# ANALOG_TRIAC.net
KiCad netlist of a schematic drawn in Altium Designer
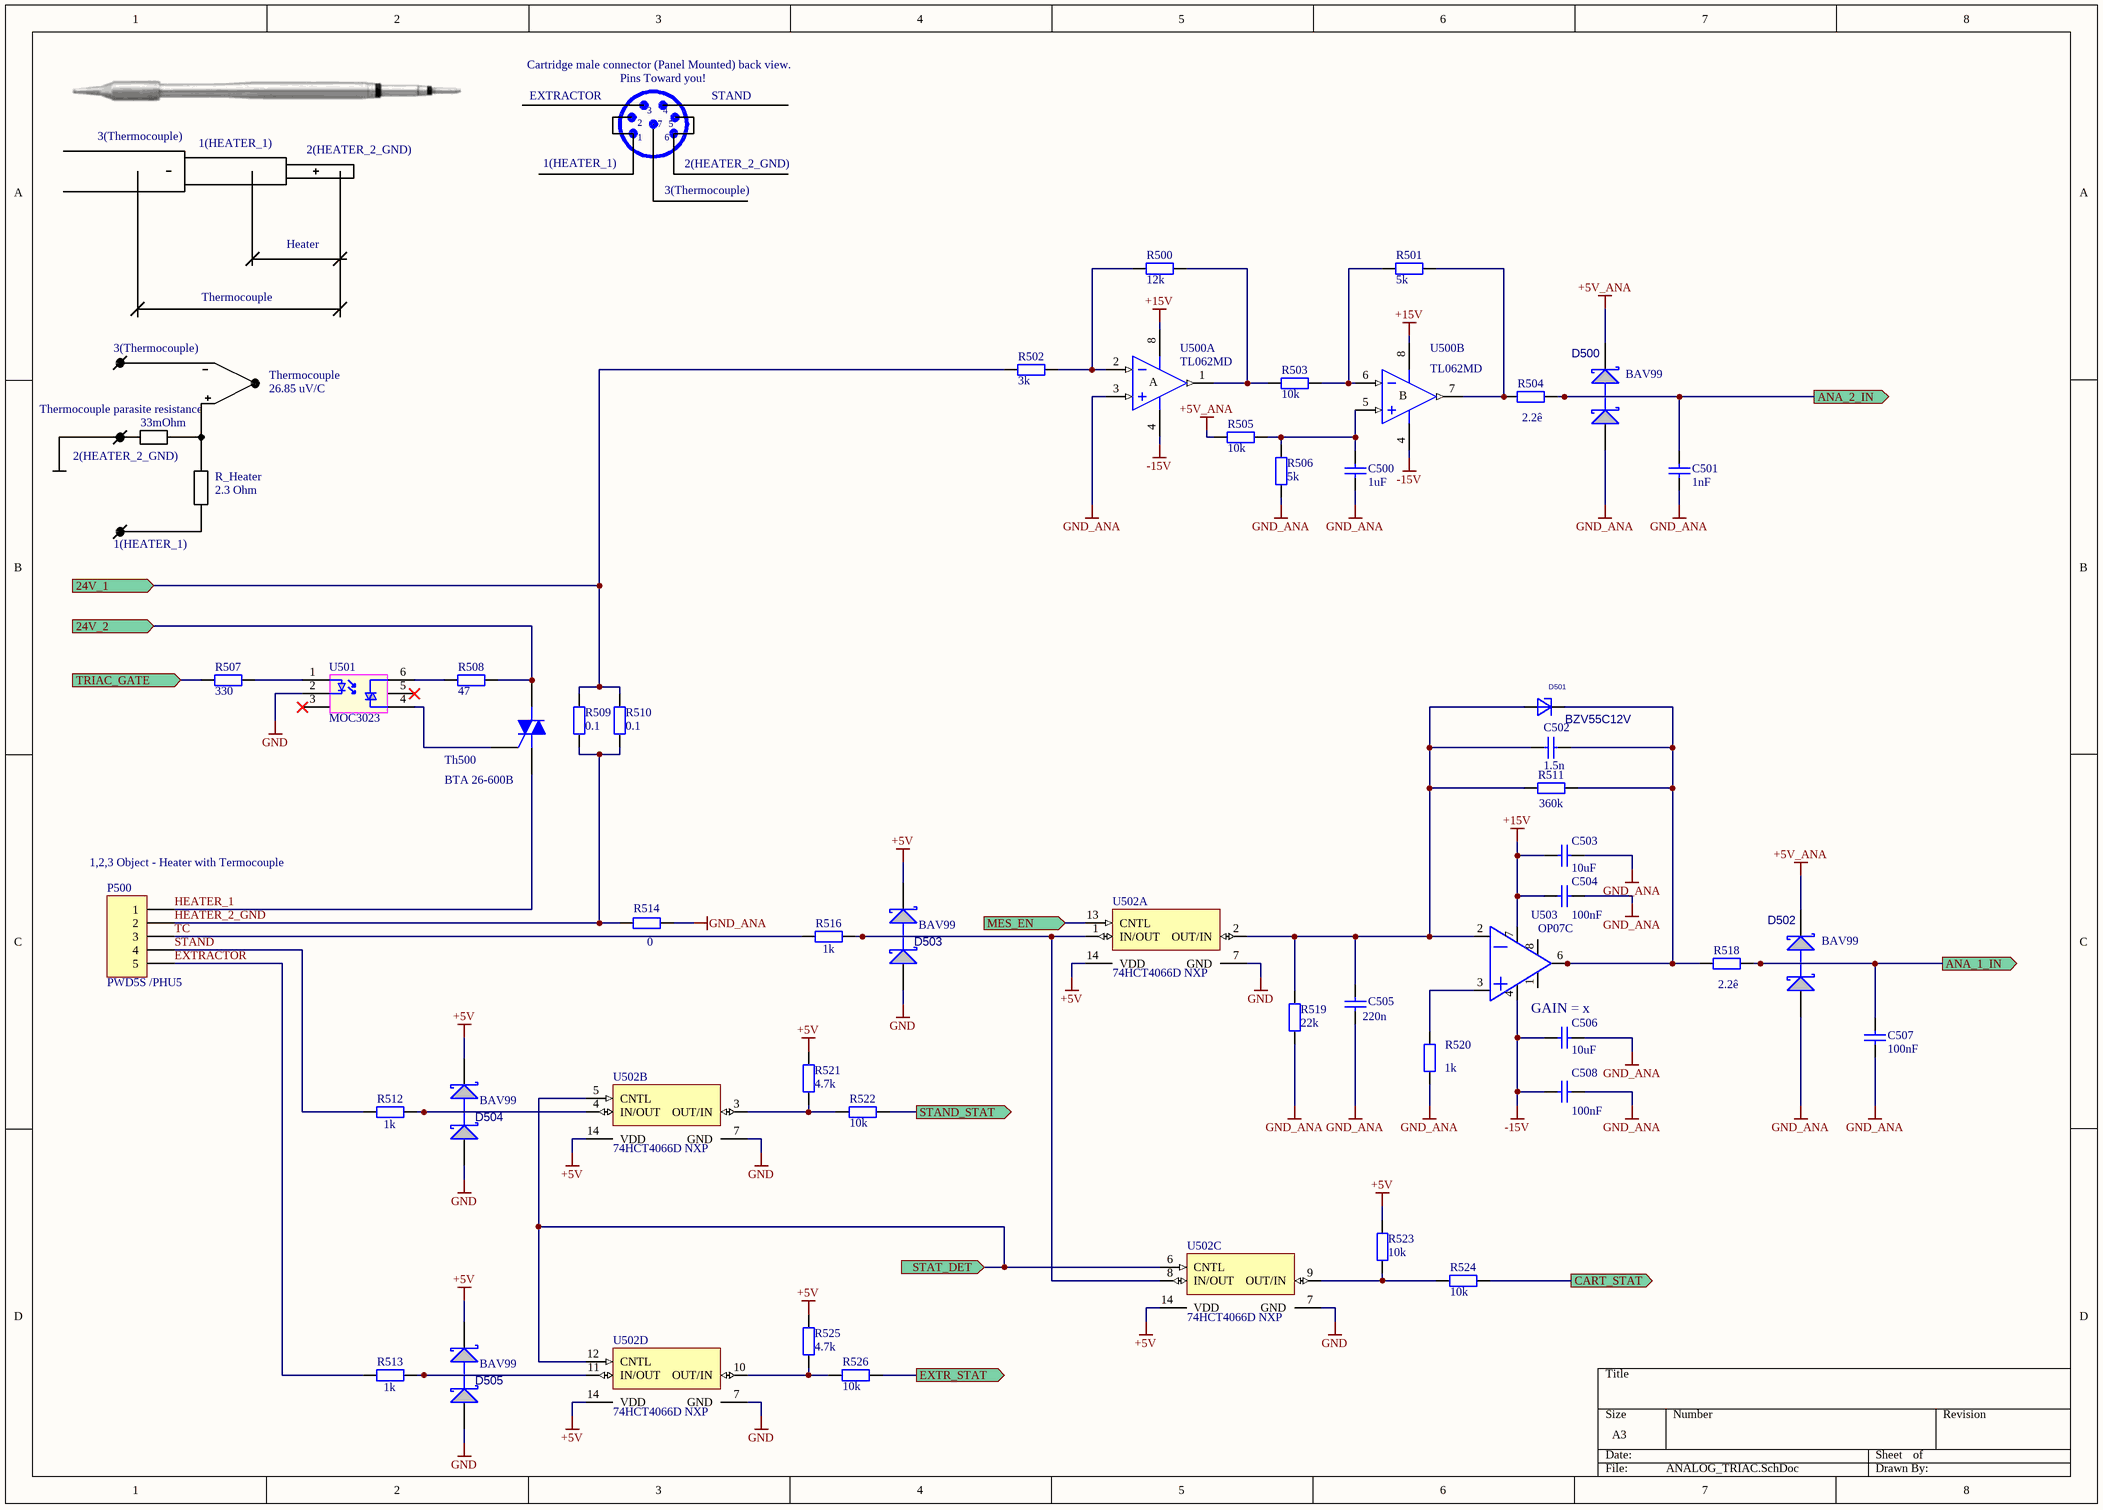
[diagram p0: ANALOG_TRIAC.SchDoc]

(export (version "E")
  (design (tool "Eeschema 10.0.6"))
  (components
    (comp (ref "C500")
      (value "1uF")
      (footprint "3216[1206]")
      (fields (field (name "Comment") "Cap 1206"))
      (libsource (lib "Capacitors") (part "Cap 1206"))
    )
    (comp (ref "C501")
      (value "1nF")
      (footprint "3216[1206]")
      (fields (field (name "Comment") "Cap 1206"))
      (libsource (lib "Capacitors") (part "Cap 1206"))
    )
    (comp (ref "C502")
      (value "1.5n")
      (footprint "3216[1206]")
      (fields (field (name "Comment") "Cap 1206"))
      (libsource (lib "Capacitors") (part "Cap 1206"))
    )
    (comp (ref "C503")
      (value "10uF")
      (footprint "3216[1206]")
      (fields (field (name "Comment") "Cap 1206"))
      (libsource (lib "Capacitors") (part "Cap 1206"))
    )
    (comp (ref "C504")
      (value "100nF")
      (footprint "3216[1206]")
      (fields (field (name "Comment") "Cap 1206"))
      (libsource (lib "Capacitors") (part "Cap 1206"))
    )
    (comp (ref "C505")
      (value "220n")
      (footprint "3216[1206]")
      (fields (field (name "Comment") "Cap 1206"))
      (libsource (lib "Capacitors") (part "Cap 1206"))
    )
    (comp (ref "C506")
      (value "10uF")
      (footprint "3216[1206]")
      (fields (field (name "Comment") "Cap 1206"))
      (libsource (lib "Capacitors") (part "Cap 1206"))
    )
    (comp (ref "C507")
      (value "100nF")
      (footprint "3216[1206]")
      (fields (field (name "Comment") "Cap 1206"))
      (libsource (lib "Capacitors") (part "Cap 1206"))
    )
    (comp (ref "C508")
      (value "100nF")
      (footprint "3216[1206]")
      (fields (field (name "Comment") "Cap 1206"))
      (libsource (lib "Capacitors") (part "Cap 1206"))
    )
    (comp (ref "D500")
      (value "BAV99")
      (footprint "SOT23_HIS_Primary")
      (description "Silicon Schottky Diodes")
      (fields
        (field (name "MANUFACTURER") "INF")
        (field (name "Comment") "BAT64-04")
        (field (name "PUBLISHER") "Altium Limited")
      )
      (libsource (lib "Diode") (part "BAT64-04"))
    )
    (comp (ref "D501")
      (value "BZV55C12V")
      (footprint "D_MINIMELF_BZV55C12V(Primary)")
      (libsource (lib "Zener") (part "BZV55C12V"))
    )
    (comp (ref "D502")
      (value "BAV99")
      (footprint "SOT23_HIS_Primary")
      (description "Silicon Schottky Diodes")
      (fields
        (field (name "MANUFACTURER") "INF")
        (field (name "Comment") "BAT64-04")
        (field (name "PUBLISHER") "Altium Limited")
      )
      (libsource (lib "Diode") (part "BAT64-04"))
    )
    (comp (ref "D503")
      (value "BAV99")
      (footprint "SOT23_HIS_Primary")
      (description "Silicon Schottky Diodes")
      (fields
        (field (name "MANUFACTURER") "INF")
        (field (name "Comment") "BAT64-04")
        (field (name "PUBLISHER") "Altium Limited")
      )
      (libsource (lib "Diode") (part "BAT64-04"))
    )
    (comp (ref "D504")
      (value "BAV99")
      (footprint "SOT23_HIS_Primary")
      (description "Silicon Schottky Diodes")
      (fields
        (field (name "MANUFACTURER") "INF")
        (field (name "Comment") "BAT64-04")
        (field (name "PUBLISHER") "Altium Limited")
      )
      (libsource (lib "Diode") (part "BAT64-04"))
    )
    (comp (ref "D505")
      (value "BAV99")
      (footprint "SOT23_HIS_Primary")
      (description "Silicon Schottky Diodes")
      (fields
        (field (name "MANUFACTURER") "INF")
        (field (name "Comment") "BAT64-04")
        (field (name "PUBLISHER") "Altium Limited")
      )
      (libsource (lib "Diode") (part "BAT64-04"))
    )
    (comp (ref "P500")
      (value "PWD5S /PHU5")
      (footprint "PWD5S/ PHU5")
      (libsource (lib "Connector") (part "PWD5S /PHU5"))
    )
    (comp (ref "R500")
      (value "12k")
      (footprint "1206_REFLOW")
      (fields (field (name "Comment") "RES"))
      (libsource (lib "Resistor") (part "RES 1"))
    )
    (comp (ref "R501")
      (value "5k")
      (footprint "1206_REFLOW")
      (fields (field (name "Comment") "RES"))
      (libsource (lib "Resistor") (part "RES 1"))
    )
    (comp (ref "R502")
      (value "3k")
      (footprint "1206_REFLOW")
      (fields (field (name "Comment") "RES"))
      (libsource (lib "Resistor") (part "RES 1"))
    )
    (comp (ref "R503")
      (value "10k")
      (footprint "1206_REFLOW")
      (fields (field (name "Comment") "RES"))
      (libsource (lib "Resistor") (part "RES 1"))
    )
    (comp (ref "R504")
      (value "2.2ê")
      (footprint "3216[1206]")
      (fields (field (name "Comment") "RES"))
      (libsource (lib "Resistor") (part "RES 1"))
    )
    (comp (ref "R505")
      (value "10k")
      (footprint "1206_REFLOW")
      (fields (field (name "Comment") "RES"))
      (libsource (lib "Resistor") (part "RES 1"))
    )
    (comp (ref "R506")
      (value "5k")
      (footprint "1206_REFLOW")
      (fields (field (name "Comment") "RES"))
      (libsource (lib "") (part "RES 1_1"))
    )
    (comp (ref "R507")
      (value "330")
      (footprint "3216[1206]")
      (fields (field (name "Comment") "RES"))
      (libsource (lib "Resistor") (part "RES 1"))
    )
    (comp (ref "R508")
      (value "47")
      (footprint "3216[1206]")
      (fields (field (name "Comment") "RES"))
      (libsource (lib "Resistor") (part "RES 1"))
    )
    (comp (ref "R509")
      (value "0.1")
      (footprint "RA161004")
      (fields (field (name "Comment") "RES"))
      (libsource (lib "") (part "RES 1_2"))
    )
    (comp (ref "R510")
      (value "0.1")
      (footprint "RA161004")
      (fields (field (name "Comment") "RES"))
      (libsource (lib "") (part "RES 1_2"))
    )
    (comp (ref "R511")
      (value "360k")
      (footprint "3216[1206]")
      (fields (field (name "Comment") "RES"))
      (libsource (lib "Resistor") (part "RES 1"))
    )
    (comp (ref "R512")
      (value "1k")
      (footprint "3216[1206]")
      (fields (field (name "Comment") "RES"))
      (libsource (lib "Resistor") (part "RES 1"))
    )
    (comp (ref "R513")
      (value "1k")
      (footprint "3216[1206]")
      (fields (field (name "Comment") "RES"))
      (libsource (lib "Resistor") (part "RES 1"))
    )
    (comp (ref "R514")
      (value "0")
      (footprint "1206_REFLOW")
      (fields (field (name "Comment") "RES"))
      (libsource (lib "Resistor") (part "RES 1"))
    )
    (comp (ref "R516")
      (value "1k")
      (footprint "3216[1206]")
      (fields (field (name "Comment") "RES"))
      (libsource (lib "Resistor") (part "RES 1"))
    )
    (comp (ref "R518")
      (value "2.2ê")
      (footprint "3216[1206]")
      (fields (field (name "Comment") "RES"))
      (libsource (lib "Resistor") (part "RES 1"))
    )
    (comp (ref "R519")
      (value "22k")
      (footprint "3216[1206]")
      (fields (field (name "Comment") "RES"))
      (libsource (lib "") (part "RES 1_2"))
    )
    (comp (ref "R520")
      (value "1k")
      (footprint "3216[1206]")
      (fields (field (name "Comment") "RES"))
      (libsource (lib "") (part "RES 1_2"))
    )
    (comp (ref "R521")
      (value "4.7k")
      (footprint "3216[1206]")
      (fields (field (name "Comment") "RES"))
      (libsource (lib "") (part "RES 1_1"))
    )
    (comp (ref "R522")
      (value "10k")
      (footprint "3216[1206]")
      (fields (field (name "Comment") "RES"))
      (libsource (lib "Resistor") (part "RES 1"))
    )
    (comp (ref "R523")
      (value "10k")
      (footprint "3216[1206]")
      (fields (field (name "Comment") "RES"))
      (libsource (lib "") (part "RES 1_1"))
    )
    (comp (ref "R524")
      (value "10k")
      (footprint "3216[1206]")
      (fields (field (name "Comment") "RES"))
      (libsource (lib "Resistor") (part "RES 1"))
    )
    (comp (ref "R525")
      (value "4.7k")
      (footprint "3216[1206]")
      (fields (field (name "Comment") "RES"))
      (libsource (lib "") (part "RES 1_1"))
    )
    (comp (ref "R526")
      (value "10k")
      (footprint "3216[1206]")
      (fields (field (name "Comment") "RES"))
      (libsource (lib "Resistor") (part "RES 1"))
    )
    (comp (ref "Th500")
      (value "BTA 26-600B")
      (footprint "TO247")
      (libsource (lib "Thyristor") (part "BTA 26-600B"))
    )
    (comp (ref "U500")
      (value "TL062MD")
      (footprint "SO8_N")
      (description "Low-Power J-FET Dual Bipolar Operational Amplifier")
      (fields (field (name "PUBLISHER") "Altium Limited"))
      (libsource (lib "ST Operational Amplifier") (part "TL062MD"))
    )
    (comp (ref "U501") (value "MOC3023") (footprint "DIP-6") (libsource (lib "Optocoupler") (part "MOC3023")))
    (comp (ref "U502")
      (value "74HCT4066D NXP")
      (footprint "SO14_N")
      (description "Quad Bilateral Switch For Transmission or Multiplexing of Analog or Digital Signals")
      (fields (field (name "PUBLISHER") "Altium Limited"))
      (libsource (lib "ST Logic Switch") (part "HCF4066BM1"))
    )
    (comp (ref "U503") (value "OP07C") (footprint "SO8") (libsource (lib "OpAmp") (part "OP07C")))
  )
  (nets
    (net (code "1") (name "+5V") (class "Default")
      (node (ref "D503") (pin "2") (pinfunction "K_2") (pintype "passive"))
      (node (ref "D504") (pin "2") (pinfunction "K_2") (pintype "passive"))
      (node (ref "D505") (pin "2") (pinfunction "K_2") (pintype "passive"))
      (node (ref "R521") (pin "2") (pinfunction "2_2") (pintype "passive"))
      (node (ref "R523") (pin "2") (pinfunction "2_2") (pintype "passive"))
      (node (ref "R525") (pin "2") (pinfunction "2_2") (pintype "passive"))
      (node (ref "U502") (pin "14") (pinfunction "VDD_14") (pintype "power_in"))
    )
    (net (code "2") (name "+5V_ANA") (class "Default")
      (node (ref "D500") (pin "2") (pinfunction "K_2") (pintype "passive"))
      (node (ref "D502") (pin "2") (pinfunction "K_2") (pintype "passive"))
      (node (ref "R505") (pin "1") (pinfunction "1_1") (pintype "passive"))
    )
    (net (code "3") (name "+15V") (class "Default")
      (node (ref "C503") (pin "2") (pinfunction "2_2") (pintype "passive"))
      (node (ref "C504") (pin "2") (pinfunction "2_2") (pintype "passive"))
      (node (ref "U500") (pin "8") (pinfunction "V+_8") (pintype "power_in"))
      (node (ref "U503") (pin "7") (pinfunction "7_7") (pintype "passive"))
    )
    (net (code "4") (name "-15V") (class "Default")
      (node (ref "C506") (pin "2") (pinfunction "2_2") (pintype "passive"))
      (node (ref "C508") (pin "2") (pinfunction "2_2") (pintype "passive"))
      (node (ref "U500") (pin "4") (pinfunction "V-_4") (pintype "power_in"))
      (node (ref "U503") (pin "4") (pinfunction "4_4") (pintype "passive"))
    )
    (net (code "5") (name "/24V_1") (class "Default")
      (node (ref "R502") (pin "1") (pinfunction "1_1") (pintype "passive"))
      (node (ref "R509") (pin "1") (pinfunction "1_1") (pintype "passive"))
      (node (ref "R510") (pin "1") (pinfunction "1_1") (pintype "passive"))
    )
    (net (code "6") (name "/24V_2") (class "Default")
      (node (ref "R508") (pin "2") (pinfunction "2_2") (pintype "passive"))
      (node (ref "Th500") (pin "2") (pinfunction "2_2") (pintype "passive"))
    )
    (net (code "7") (name "/ANA_1_IN") (class "Default")
      (node (ref "C507") (pin "2") (pinfunction "2_2") (pintype "passive"))
      (node (ref "D502") (pin "3") (pinfunction "C_3") (pintype "passive"))
      (node (ref "R518") (pin "2") (pinfunction "2_2") (pintype "passive"))
    )
    (net (code "8") (name "/ANA_2_IN") (class "Default")
      (node (ref "C501") (pin "2") (pinfunction "2_2") (pintype "passive"))
      (node (ref "D500") (pin "3") (pinfunction "C_3") (pintype "passive"))
      (node (ref "R504") (pin "2") (pinfunction "2_2") (pintype "passive"))
    )
    (net (code "9") (name "/CART_STAT") (class "Default")
      (node (ref "R524") (pin "2") (pinfunction "2_2") (pintype "passive"))
    )
    (net (code "10") (name "/EXTRACTOR") (class "Default")
      (node (ref "P500") (pin "5") (pinfunction "5_5") (pintype "passive"))
      (node (ref "R513") (pin "1") (pinfunction "1_1") (pintype "passive"))
    )
    (net (code "11") (name "/EXTR_STAT") (class "Default")
      (node (ref "R526") (pin "2") (pinfunction "2_2") (pintype "passive"))
    )
    (net (code "12") (name "/HEATER_1") (class "Default")
      (node (ref "P500") (pin "1") (pinfunction "1_1") (pintype "passive"))
      (node (ref "Th500") (pin "1") (pinfunction "1_1") (pintype "passive"))
    )
    (net (code "13") (name "/HEATER_2_GND") (class "Default")
      (node (ref "P500") (pin "2") (pinfunction "2_2") (pintype "passive"))
      (node (ref "R509") (pin "2") (pinfunction "2_2") (pintype "passive"))
      (node (ref "R510") (pin "2") (pinfunction "2_2") (pintype "passive"))
      (node (ref "R514") (pin "1") (pinfunction "1_1") (pintype "passive"))
    )
    (net (code "14") (name "/MES_EN") (class "Default")
      (node (ref "U502") (pin "13") (pinfunction "CNTL_13") (pintype "input"))
    )
    (net (code "15") (name "/STAND") (class "Default")
      (node (ref "P500") (pin "4") (pinfunction "4_4") (pintype "passive"))
      (node (ref "R512") (pin "1") (pinfunction "1_1") (pintype "passive"))
    )
    (net (code "16") (name "/STAND_STAT") (class "Default")
      (node (ref "R522") (pin "2") (pinfunction "2_2") (pintype "passive"))
    )
    (net (code "17") (name "/STAT_DET") (class "Default")
      (node (ref "U502") (pin "12") (pinfunction "CNTL_12") (pintype "input"))
      (node (ref "U502") (pin "5") (pinfunction "CNTL_5") (pintype "input"))
      (node (ref "U502") (pin "6") (pinfunction "CNTL_6") (pintype "input"))
    )
    (net (code "18") (name "/TC") (class "Default")
      (node (ref "P500") (pin "3") (pinfunction "3_3") (pintype "passive"))
      (node (ref "R516") (pin "1") (pinfunction "1_1") (pintype "passive"))
    )
    (net (code "19") (name "/TRIAC_GATE") (class "Default")
      (node (ref "R507") (pin "1") (pinfunction "1_1") (pintype "passive"))
    )
    (net (code "20") (name "GND") (class "Default")
      (node (ref "D503") (pin "1") (pinfunction "A_1") (pintype "passive"))
      (node (ref "D504") (pin "1") (pinfunction "A_1") (pintype "passive"))
      (node (ref "D505") (pin "1") (pinfunction "A_1") (pintype "passive"))
      (node (ref "U501") (pin "2") (pinfunction "2_2") (pintype "passive"))
      (node (ref "U502") (pin "7") (pinfunction "GND_7") (pintype "power_in"))
    )
    (net (code "21") (name "GND_ANA") (class "Default")
      (node (ref "C500") (pin "1") (pinfunction "1_1") (pintype "passive"))
      (node (ref "C501") (pin "1") (pinfunction "1_1") (pintype "passive"))
      (node (ref "C503") (pin "1") (pinfunction "1_1") (pintype "passive"))
      (node (ref "C504") (pin "1") (pinfunction "1_1") (pintype "passive"))
      (node (ref "C505") (pin "1") (pinfunction "1_1") (pintype "passive"))
      (node (ref "C506") (pin "1") (pinfunction "1_1") (pintype "passive"))
      (node (ref "C507") (pin "1") (pinfunction "1_1") (pintype "passive"))
      (node (ref "C508") (pin "1") (pinfunction "1_1") (pintype "passive"))
      (node (ref "D500") (pin "1") (pinfunction "A_1") (pintype "passive"))
      (node (ref "D502") (pin "1") (pinfunction "A_1") (pintype "passive"))
      (node (ref "R506") (pin "1") (pinfunction "1_1") (pintype "passive"))
      (node (ref "R514") (pin "2") (pinfunction "2_2") (pintype "passive"))
      (node (ref "R519") (pin "2") (pinfunction "2_2") (pintype "passive"))
      (node (ref "R520") (pin "2") (pinfunction "2_2") (pintype "passive"))
      (node (ref "U500") (pin "3") (pinfunction "IN+_3") (pintype "input"))
    )
    (net (code "22") (name "Net-(C502-Pad1)") (class "Default")
      (node (ref "C502") (pin "1") (pinfunction "1_1") (pintype "passive"))
      (node (ref "D501") (pin "K") (pintype "passive"))
      (node (ref "R511") (pin "2") (pinfunction "2_2") (pintype "passive"))
      (node (ref "R518") (pin "1") (pinfunction "1_1") (pintype "passive"))
      (node (ref "U503") (pin "6") (pinfunction "6_6") (pintype "passive"))
    )
    (net (code "23") (name "Net-(D503-C)") (class "Default")
      (node (ref "D503") (pin "3") (pinfunction "C_3") (pintype "passive"))
      (node (ref "R516") (pin "2") (pinfunction "2_2") (pintype "passive"))
      (node (ref "U502") (pin "1") (pinfunction "IN/OUT_1") (pintype "bidirectional"))
      (node (ref "U502") (pin "8") (pinfunction "IN/OUT_8") (pintype "bidirectional"))
    )
    (net (code "24") (name "Net-(D504-C)") (class "Default")
      (node (ref "D504") (pin "3") (pinfunction "C_3") (pintype "passive"))
      (node (ref "R512") (pin "2") (pinfunction "2_2") (pintype "passive"))
      (node (ref "U502") (pin "4") (pinfunction "IN/OUT_4") (pintype "bidirectional"))
    )
    (net (code "25") (name "Net-(D505-C)") (class "Default")
      (node (ref "D505") (pin "3") (pinfunction "C_3") (pintype "passive"))
      (node (ref "R513") (pin "2") (pinfunction "2_2") (pintype "passive"))
      (node (ref "U502") (pin "11") (pinfunction "IN/OUT_11") (pintype "bidirectional"))
    )
    (net (code "26") (name "Net-(R507-Pad2)") (class "Default")
      (node (ref "R507") (pin "2") (pinfunction "2_2") (pintype "passive"))
      (node (ref "U501") (pin "1") (pinfunction "1_1") (pintype "passive"))
    )
    (net (code "27") (name "Net-(R508-Pad1)") (class "Default")
      (node (ref "R508") (pin "1") (pinfunction "1_1") (pintype "passive"))
      (node (ref "U501") (pin "6") (pinfunction "6_6") (pintype "passive"))
    )
    (net (code "28") (name "Net-(R520-Pad1)") (class "Default")
      (node (ref "R520") (pin "1") (pinfunction "1_1") (pintype "passive"))
      (node (ref "U503") (pin "3") (pinfunction "3_3") (pintype "passive"))
    )
    (net (code "29") (name "Net-(Th500-Pad3)") (class "Default")
      (node (ref "Th500") (pin "3") (pinfunction "3_3") (pintype "passive"))
      (node (ref "U501") (pin "4") (pinfunction "4_4") (pintype "passive"))
    )
    (net (code "30") (name "Net-(U500A-IN-)") (class "Default")
      (node (ref "R500") (pin "1") (pinfunction "1_1") (pintype "passive"))
      (node (ref "R502") (pin "2") (pinfunction "2_2") (pintype "passive"))
      (node (ref "U500") (pin "2") (pinfunction "IN-_2") (pintype "input"))
    )
    (net (code "31") (name "Net-(U500A-OUT)") (class "Default")
      (node (ref "R500") (pin "2") (pinfunction "2_2") (pintype "passive"))
      (node (ref "R503") (pin "1") (pinfunction "1_1") (pintype "passive"))
      (node (ref "U500") (pin "1") (pinfunction "OUT_1") (pintype "output"))
    )
    (net (code "32") (name "Net-(U500B-IN+)") (class "Default")
      (node (ref "C500") (pin "2") (pinfunction "2_2") (pintype "passive"))
      (node (ref "R505") (pin "2") (pinfunction "2_2") (pintype "passive"))
      (node (ref "R506") (pin "2") (pinfunction "2_2") (pintype "passive"))
      (node (ref "U500") (pin "5") (pinfunction "IN+_5") (pintype "input"))
    )
    (net (code "33") (name "Net-(U500B-IN-)") (class "Default")
      (node (ref "R501") (pin "1") (pinfunction "1_1") (pintype "passive"))
      (node (ref "R503") (pin "2") (pinfunction "2_2") (pintype "passive"))
      (node (ref "U500") (pin "6") (pinfunction "IN-_6") (pintype "input"))
    )
    (net (code "34") (name "Net-(U500B-OUT)") (class "Default")
      (node (ref "R501") (pin "2") (pinfunction "2_2") (pintype "passive"))
      (node (ref "R504") (pin "1") (pinfunction "1_1") (pintype "passive"))
      (node (ref "U500") (pin "7") (pinfunction "OUT_7") (pintype "output"))
    )
    (net (code "35") (name "Net-(U502A-OUT{slash}IN)") (class "Default")
      (node (ref "C502") (pin "2") (pinfunction "2_2") (pintype "passive"))
      (node (ref "C505") (pin "2") (pinfunction "2_2") (pintype "passive"))
      (node (ref "D501") (pin "A") (pintype "passive"))
      (node (ref "R511") (pin "1") (pinfunction "1_1") (pintype "passive"))
      (node (ref "R519") (pin "1") (pinfunction "1_1") (pintype "passive"))
      (node (ref "U502") (pin "2") (pinfunction "OUT/IN_2") (pintype "bidirectional"))
      (node (ref "U503") (pin "2") (pinfunction "2_2") (pintype "passive"))
    )
    (net (code "36") (name "Net-(U502B-OUT{slash}IN)") (class "Default")
      (node (ref "R521") (pin "1") (pinfunction "1_1") (pintype "passive"))
      (node (ref "R522") (pin "1") (pinfunction "1_1") (pintype "passive"))
      (node (ref "U502") (pin "3") (pinfunction "OUT/IN_3") (pintype "bidirectional"))
    )
    (net (code "37") (name "Net-(U502C-OUT{slash}IN)") (class "Default")
      (node (ref "R523") (pin "1") (pinfunction "1_1") (pintype "passive"))
      (node (ref "R524") (pin "1") (pinfunction "1_1") (pintype "passive"))
      (node (ref "U502") (pin "9") (pinfunction "OUT/IN_9") (pintype "bidirectional"))
    )
    (net (code "38") (name "Net-(U502D-OUT{slash}IN)") (class "Default")
      (node (ref "R525") (pin "1") (pinfunction "1_1") (pintype "passive"))
      (node (ref "R526") (pin "1") (pinfunction "1_1") (pintype "passive"))
      (node (ref "U502") (pin "10") (pinfunction "OUT/IN_10") (pintype "bidirectional"))
    )
    (net (code "39") (name "unconnected-(U501-Pad3)") (class "Default")
      (node (ref "U501") (pin "3") (pinfunction "3_3") (pintype "passive+no_connect"))
    )
    (net (code "40") (name "unconnected-(U501-Pad5)") (class "Default")
      (node (ref "U501") (pin "5") (pinfunction "5_5") (pintype "passive+no_connect"))
    )
    (net (code "41") (name "unconnected-(U503-Pad1)") (class "Default")
      (node (ref "U503") (pin "1") (pinfunction "1_1") (pintype "passive"))
    )
    (net (code "42") (name "unconnected-(U503-Pad8)") (class "Default")
      (node (ref "U503") (pin "8") (pinfunction "8_8") (pintype "passive"))
    )
  )
)
